# oresat-camera-board-v1.net
KiCad netlist of a schematic drawn in EAGLE
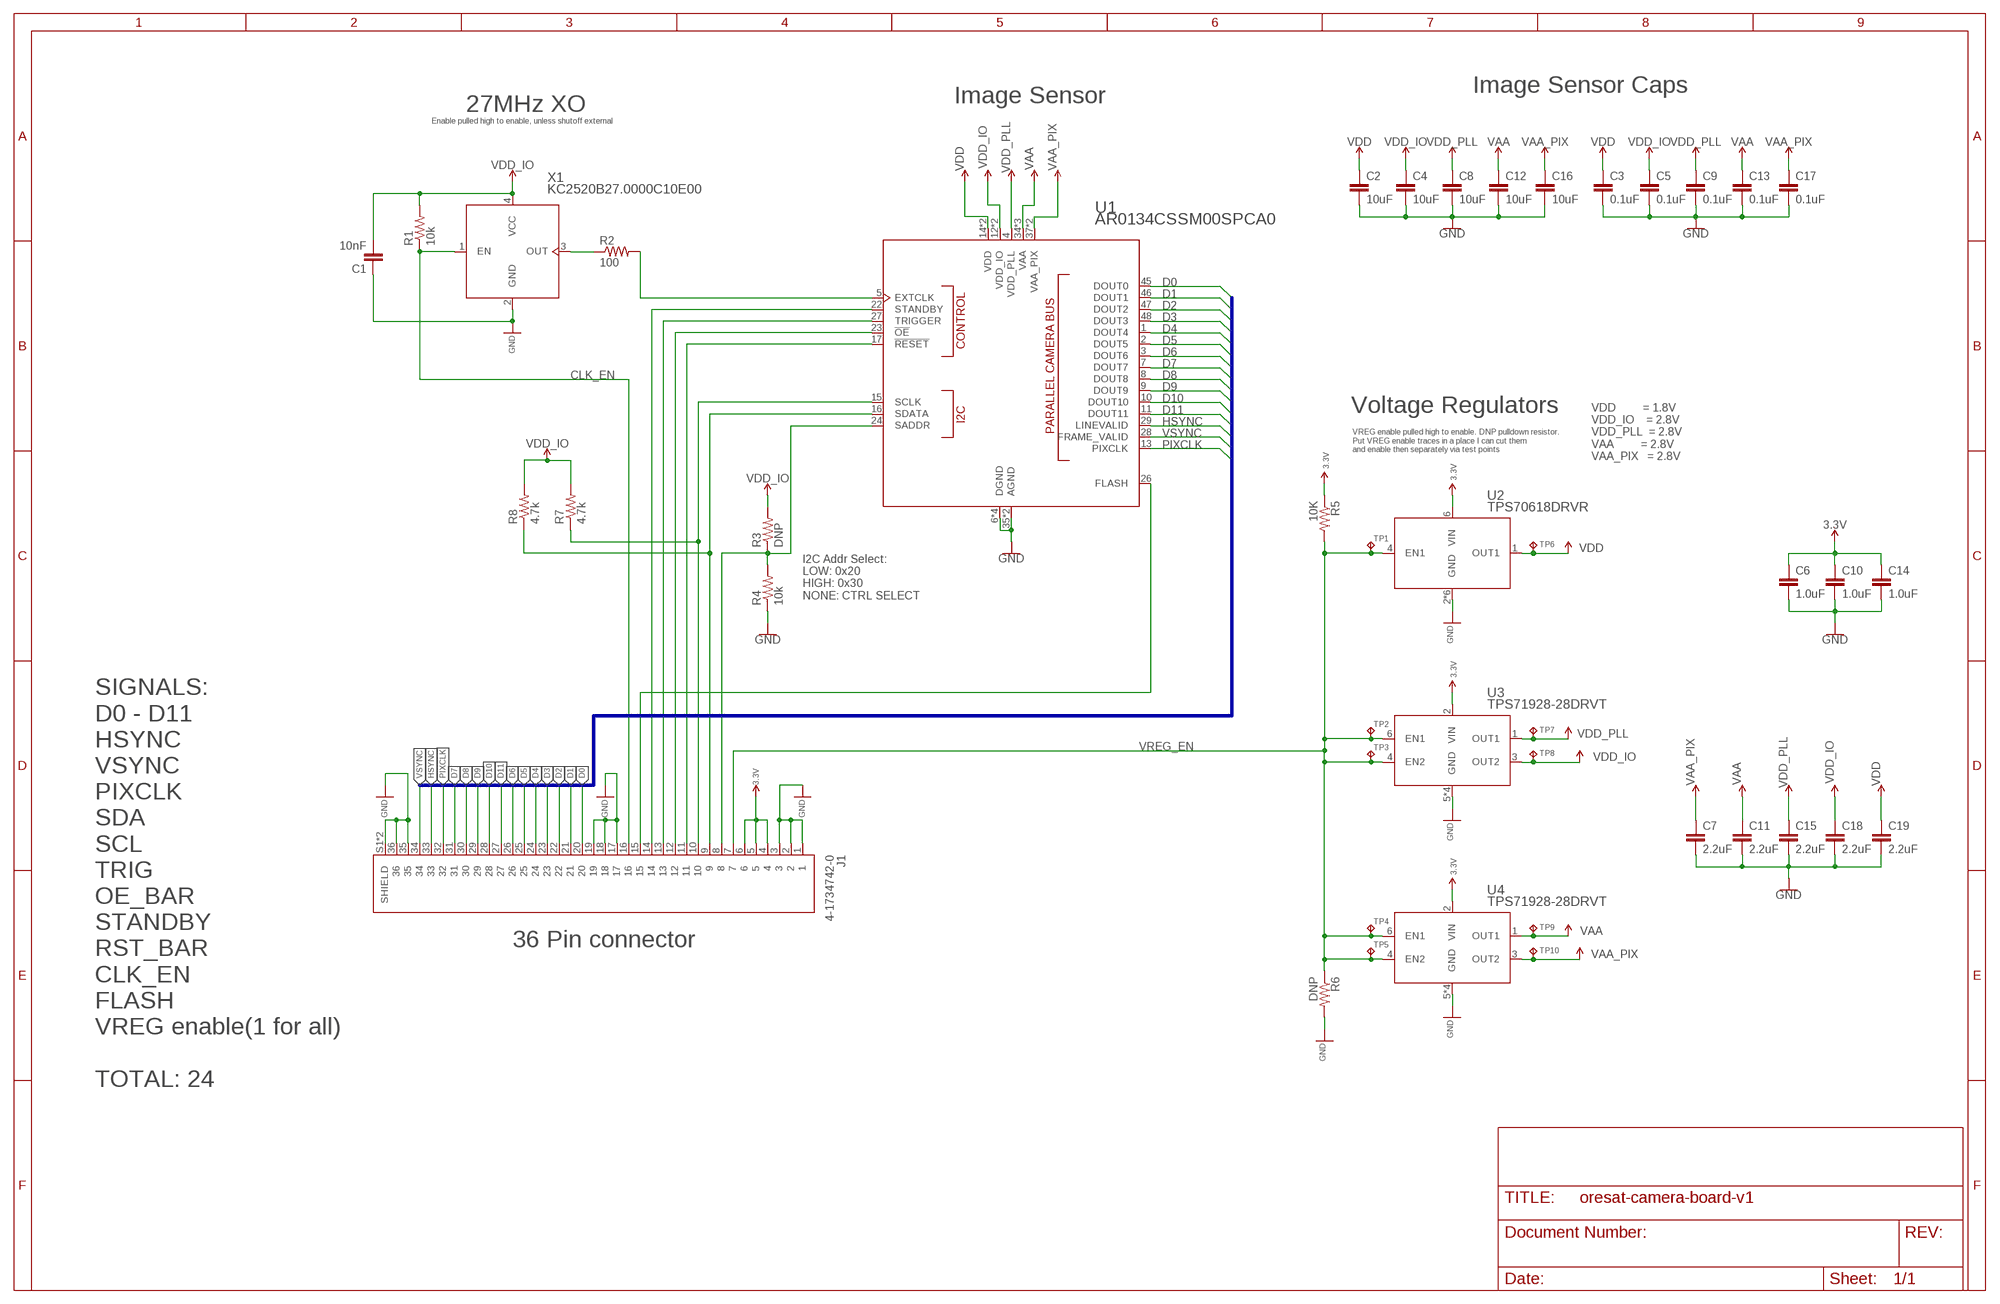
[diagram p0: schematic, sheet 1]

(export (version "E")
  (design (tool "Eeschema 10.0.6"))
  (components
    (comp (ref "C1")
      (value "10nF")
      (footprint "eagle-import:.0402-A-NOSILK")
      (libsource (lib "eagle-import") (part "C-EU0402-A-NOSILK"))
    )
    (comp (ref "C2")
      (value "10uF")
      (footprint "eagle-import:.0603-C-NOSILK")
      (libsource (lib "eagle-import") (part "C-EU0603-C-NOSILK"))
    )
    (comp (ref "C3")
      (value "0.1uF")
      (footprint "eagle-import:.0402-B-NOSILK")
      (libsource (lib "eagle-import") (part "C-EU0402-B-NOSILK"))
    )
    (comp (ref "C4")
      (value "10uF")
      (footprint "eagle-import:.0603-C-NOSILK")
      (libsource (lib "eagle-import") (part "C-EU0603-C-NOSILK"))
    )
    (comp (ref "C5")
      (value "0.1uF")
      (footprint "eagle-import:.0402-B-NOSILK")
      (libsource (lib "eagle-import") (part "C-EU0402-B-NOSILK"))
    )
    (comp (ref "C6")
      (value "1.0uF")
      (footprint "eagle-import:.0603-C-NOSILK")
      (libsource (lib "eagle-import") (part "C-EU0603-C-NOSILK"))
    )
    (comp (ref "C7")
      (value "2.2uF")
      (footprint "eagle-import:.0603-C-NOSILK")
      (libsource (lib "eagle-import") (part "C-EU0603-C-NOSILK"))
    )
    (comp (ref "C8")
      (value "10uF")
      (footprint "eagle-import:.0603-C-NOSILK")
      (libsource (lib "eagle-import") (part "C-EU0603-C-NOSILK"))
    )
    (comp (ref "C9")
      (value "0.1uF")
      (footprint "eagle-import:.0402-B-NOSILK")
      (libsource (lib "eagle-import") (part "C-EU0402-B-NOSILK"))
    )
    (comp (ref "C10")
      (value "1.0uF")
      (footprint "eagle-import:.0603-C-NOSILK")
      (libsource (lib "eagle-import") (part "C-EU0603-C-NOSILK"))
    )
    (comp (ref "C11")
      (value "2.2uF")
      (footprint "eagle-import:.0603-C-NOSILK")
      (libsource (lib "eagle-import") (part "C-EU0603-C-NOSILK"))
    )
    (comp (ref "C12")
      (value "10uF")
      (footprint "eagle-import:.0603-C-NOSILK")
      (libsource (lib "eagle-import") (part "C-EU0603-C-NOSILK"))
    )
    (comp (ref "C13")
      (value "0.1uF")
      (footprint "eagle-import:.0402-B-NOSILK")
      (libsource (lib "eagle-import") (part "C-EU0402-B-NOSILK"))
    )
    (comp (ref "C14")
      (value "1.0uF")
      (footprint "eagle-import:.0603-C-NOSILK")
      (libsource (lib "eagle-import") (part "C-EU0603-C-NOSILK"))
    )
    (comp (ref "C15")
      (value "2.2uF")
      (footprint "eagle-import:.0603-C-NOSILK")
      (libsource (lib "eagle-import") (part "C-EU0603-C-NOSILK"))
    )
    (comp (ref "C16")
      (value "10uF")
      (footprint "eagle-import:.0603-C-NOSILK")
      (libsource (lib "eagle-import") (part "C-EU0603-C-NOSILK"))
    )
    (comp (ref "C17")
      (value "0.1uF")
      (footprint "eagle-import:.0402-B-NOSILK")
      (libsource (lib "eagle-import") (part "C-EU0402-B-NOSILK"))
    )
    (comp (ref "C18")
      (value "2.2uF")
      (footprint "eagle-import:.0603-C-NOSILK")
      (libsource (lib "eagle-import") (part "C-EU0603-C-NOSILK"))
    )
    (comp (ref "C19")
      (value "2.2uF")
      (footprint "eagle-import:.0603-C-NOSILK")
      (libsource (lib "eagle-import") (part "C-EU0603-C-NOSILK"))
    )
    (comp (ref "J1")
      (value "4-1734742-0")
      (footprint "eagle-import:TE_4-1734742-0")
      (fields (field (name "DIGI-KEY_PART_NUMBER") "A100242CT-ND") (field (name "MF") "TE Connectivity"))
      (libsource (lib "eagle-import") (part "4-1734742-0"))
    )
    (comp (ref "R1")
      (value "10k")
      (footprint "eagle-import:.0402-B")
      (libsource (lib "eagle-import") (part "R-US_0402-B"))
    )
    (comp (ref "R2")
      (value "100")
      (footprint "eagle-import:.0402-B")
      (libsource (lib "eagle-import") (part "R-US_0402-B"))
    )
    (comp (ref "R3")
      (value "DNP")
      (footprint "eagle-import:.0402-B")
      (libsource (lib "eagle-import") (part "R-US_0402-B"))
    )
    (comp (ref "R4")
      (value "10k")
      (footprint "eagle-import:.0402-B")
      (libsource (lib "eagle-import") (part "R-US_0402-B"))
    )
    (comp (ref "R5")
      (value "10K")
      (footprint "eagle-import:.0402-B")
      (libsource (lib "eagle-import") (part "R-US_0402-B"))
    )
    (comp (ref "R6")
      (value "DNP")
      (footprint "eagle-import:.0402-B")
      (libsource (lib "eagle-import") (part "R-US_0402-B"))
    )
    (comp (ref "R7")
      (value "4.7k")
      (footprint "eagle-import:.0402-B")
      (libsource (lib "eagle-import") (part "R-US_0402-B"))
    )
    (comp (ref "R8")
      (value "4.7k")
      (footprint "eagle-import:.0402-B")
      (libsource (lib "eagle-import") (part "R-US_0402-B"))
    )
    (comp (ref "TP1")
      (value "TPTP06R")
      (footprint "eagle-import:TP06R")
      (libsource (lib "eagle-import") (part "TPTP06R"))
    )
    (comp (ref "TP2")
      (value "TPTP06R")
      (footprint "eagle-import:TP06R")
      (libsource (lib "eagle-import") (part "TPTP06R"))
    )
    (comp (ref "TP3")
      (value "TPTP06R")
      (footprint "eagle-import:TP06R")
      (libsource (lib "eagle-import") (part "TPTP06R"))
    )
    (comp (ref "TP4")
      (value "TPTP06R")
      (footprint "eagle-import:TP06R")
      (libsource (lib "eagle-import") (part "TPTP06R"))
    )
    (comp (ref "TP5")
      (value "TPTP06R")
      (footprint "eagle-import:TP06R")
      (libsource (lib "eagle-import") (part "TPTP06R"))
    )
    (comp (ref "TP6")
      (value "TPTP06R")
      (footprint "eagle-import:TP06R")
      (libsource (lib "eagle-import") (part "TPTP06R"))
    )
    (comp (ref "TP7")
      (value "TPTP06R")
      (footprint "eagle-import:TP06R")
      (libsource (lib "eagle-import") (part "TPTP06R"))
    )
    (comp (ref "TP8")
      (value "TPTP06R")
      (footprint "eagle-import:TP06R")
      (libsource (lib "eagle-import") (part "TPTP06R"))
    )
    (comp (ref "TP9")
      (value "TPTP06R")
      (footprint "eagle-import:TP06R")
      (libsource (lib "eagle-import") (part "TPTP06R"))
    )
    (comp (ref "TP10")
      (value "TPTP06R")
      (footprint "eagle-import:TP06R")
      (libsource (lib "eagle-import") (part "TPTP06R"))
    )
    (comp (ref "U1")
      (value "AR0134CSSM00SPCA0")
      (footprint "eagle-import:AR0134CSSM00SPCA0")
      (libsource (lib "eagle-import") (part "AR0134CSSM00SPCA0"))
    )
    (comp (ref "U2")
      (value "TPS70618DRVR")
      (footprint "eagle-import:DRV6_1P6X1")
      (fields (field (name "MANUFACTURER_PART_NUMBER") "TPS7192828DRVT"))
      (libsource (lib "eagle-import") (part "TPS70618DRVR"))
    )
    (comp (ref "U3")
      (value "TPS71928-28DRVT")
      (footprint "eagle-import:DRV6_1P6X1")
      (fields (field (name "MANUFACTURER_PART_NUMBER") "TPS7192828DRVT"))
      (libsource (lib "eagle-import") (part "TPS71928-28DRVT"))
    )
    (comp (ref "U4")
      (value "TPS71928-28DRVT")
      (footprint "eagle-import:DRV6_1P6X1")
      (fields (field (name "MANUFACTURER_PART_NUMBER") "TPS7192828DRVT"))
      (libsource (lib "eagle-import") (part "TPS71928-28DRVT"))
    )
    (comp (ref "X1")
      (value "KC2520B27.0000C10E00")
      (footprint "eagle-import:OSC_KYOCERA_KC2520B")
      (libsource (lib "eagle-import") (part "KC2520B27.0000C10E00"))
    )
  )
  (nets
    (net (code "1") (name "/CLK_EN") (class "Default")
      (node (ref "J1") (pin "16") (pinfunction "16_16") (pintype "passive"))
      (node (ref "R1") (pin "1") (pinfunction "1_1") (pintype "passive"))
      (node (ref "X1") (pin "1") (pinfunction "EN_1") (pintype "passive"))
    )
    (net (code "2") (name "/VREG_EN") (class "Default")
      (node (ref "J1") (pin "7") (pinfunction "7_7") (pintype "passive"))
      (node (ref "R5") (pin "2") (pinfunction "2_2") (pintype "passive"))
      (node (ref "R6") (pin "1") (pinfunction "1_1") (pintype "passive"))
      (node (ref "TP1") (pin "TP") (pinfunction "TP_TP") (pintype "input"))
      (node (ref "TP2") (pin "TP") (pinfunction "TP_TP") (pintype "input"))
      (node (ref "TP3") (pin "TP") (pinfunction "TP_TP") (pintype "input"))
      (node (ref "TP4") (pin "TP") (pinfunction "TP_TP") (pintype "input"))
      (node (ref "TP5") (pin "TP") (pinfunction "TP_TP") (pintype "input"))
      (node (ref "U2") (pin "4") (pinfunction "EN1_4") (pintype "passive"))
      (node (ref "U3") (pin "4") (pinfunction "EN2_4") (pintype "passive"))
      (node (ref "U3") (pin "6") (pinfunction "EN1_6") (pintype "passive"))
      (node (ref "U4") (pin "4") (pinfunction "EN2_4") (pintype "passive"))
      (node (ref "U4") (pin "6") (pinfunction "EN1_6") (pintype "passive"))
    )
    (net (code "3") (name "3.3V") (class "Default")
      (node (ref "C10") (pin "1") (pinfunction "1_1") (pintype "passive"))
      (node (ref "C14") (pin "1") (pinfunction "1_1") (pintype "passive"))
      (node (ref "C6") (pin "1") (pinfunction "1_1") (pintype "passive"))
      (node (ref "J1") (pin "4") (pinfunction "4_4") (pintype "passive"))
      (node (ref "J1") (pin "5") (pinfunction "5_5") (pintype "passive"))
      (node (ref "J1") (pin "6") (pinfunction "6_6") (pintype "passive"))
      (node (ref "R5") (pin "1") (pinfunction "1_1") (pintype "passive"))
      (node (ref "U2") (pin "6") (pinfunction "VIN_6") (pintype "input"))
      (node (ref "U3") (pin "2") (pinfunction "VIN_2") (pintype "power_in"))
      (node (ref "U4") (pin "2") (pinfunction "VIN_2") (pintype "power_in"))
    )
    (net (code "4") (name "D0") (class "Default")
      (node (ref "J1") (pin "20") (pinfunction "20_20") (pintype "passive"))
      (node (ref "U1") (pin "45") (pinfunction "DOUT0_45") (pintype "bidirectional"))
    )
    (net (code "5") (name "D1") (class "Default")
      (node (ref "J1") (pin "21") (pinfunction "21_21") (pintype "passive"))
      (node (ref "U1") (pin "46") (pinfunction "DOUT1_46") (pintype "bidirectional"))
    )
    (net (code "6") (name "D2") (class "Default")
      (node (ref "J1") (pin "22") (pinfunction "22_22") (pintype "passive"))
      (node (ref "U1") (pin "47") (pinfunction "DOUT2_47") (pintype "bidirectional"))
    )
    (net (code "7") (name "D3") (class "Default")
      (node (ref "J1") (pin "23") (pinfunction "23_23") (pintype "passive"))
      (node (ref "U1") (pin "48") (pinfunction "DOUT3_48") (pintype "bidirectional"))
    )
    (net (code "8") (name "D4") (class "Default")
      (node (ref "J1") (pin "24") (pinfunction "24_24") (pintype "passive"))
      (node (ref "U1") (pin "1") (pinfunction "DOUT4_1") (pintype "bidirectional"))
    )
    (net (code "9") (name "D5") (class "Default")
      (node (ref "J1") (pin "25") (pinfunction "25_25") (pintype "passive"))
      (node (ref "U1") (pin "2") (pinfunction "DOUT5_2") (pintype "bidirectional"))
    )
    (net (code "10") (name "D6") (class "Default")
      (node (ref "J1") (pin "26") (pinfunction "26_26") (pintype "passive"))
      (node (ref "U1") (pin "3") (pinfunction "DOUT6_3") (pintype "bidirectional"))
    )
    (net (code "11") (name "D7") (class "Default")
      (node (ref "J1") (pin "31") (pinfunction "31_31") (pintype "passive"))
      (node (ref "U1") (pin "7") (pinfunction "DOUT7_7") (pintype "bidirectional"))
    )
    (net (code "12") (name "D8") (class "Default")
      (node (ref "J1") (pin "30") (pinfunction "30_30") (pintype "passive"))
      (node (ref "U1") (pin "8") (pinfunction "DOUT8_8") (pintype "bidirectional"))
    )
    (net (code "13") (name "D9") (class "Default")
      (node (ref "J1") (pin "29") (pinfunction "29_29") (pintype "passive"))
      (node (ref "U1") (pin "9") (pinfunction "DOUT9_9") (pintype "bidirectional"))
    )
    (net (code "14") (name "D10") (class "Default")
      (node (ref "J1") (pin "28") (pinfunction "28_28") (pintype "passive"))
      (node (ref "U1") (pin "10") (pinfunction "DOUT10_10") (pintype "bidirectional"))
    )
    (net (code "15") (name "D11") (class "Default")
      (node (ref "J1") (pin "27") (pinfunction "27_27") (pintype "passive"))
      (node (ref "U1") (pin "11") (pinfunction "DOUT11_11") (pintype "bidirectional"))
    )
    (net (code "16") (name "GND") (class "Default")
      (node (ref "C1") (pin "1") (pinfunction "1_1") (pintype "passive"))
      (node (ref "C10") (pin "2") (pinfunction "2_2") (pintype "passive"))
      (node (ref "C11") (pin "2") (pinfunction "2_2") (pintype "passive"))
      (node (ref "C12") (pin "2") (pinfunction "2_2") (pintype "passive"))
      (node (ref "C13") (pin "2") (pinfunction "2_2") (pintype "passive"))
      (node (ref "C14") (pin "2") (pinfunction "2_2") (pintype "passive"))
      (node (ref "C15") (pin "2") (pinfunction "2_2") (pintype "passive"))
      (node (ref "C16") (pin "2") (pinfunction "2_2") (pintype "passive"))
      (node (ref "C17") (pin "2") (pinfunction "2_2") (pintype "passive"))
      (node (ref "C18") (pin "2") (pinfunction "2_2") (pintype "passive"))
      (node (ref "C19") (pin "2") (pinfunction "2_2") (pintype "passive"))
      (node (ref "C2") (pin "2") (pinfunction "2_2") (pintype "passive"))
      (node (ref "C3") (pin "2") (pinfunction "2_2") (pintype "passive"))
      (node (ref "C4") (pin "2") (pinfunction "2_2") (pintype "passive"))
      (node (ref "C5") (pin "2") (pinfunction "2_2") (pintype "passive"))
      (node (ref "C6") (pin "2") (pinfunction "2_2") (pintype "passive"))
      (node (ref "C7") (pin "2") (pinfunction "2_2") (pintype "passive"))
      (node (ref "C8") (pin "2") (pinfunction "2_2") (pintype "passive"))
      (node (ref "C9") (pin "2") (pinfunction "2_2") (pintype "passive"))
      (node (ref "J1") (pin "1") (pinfunction "1_1") (pintype "passive"))
      (node (ref "J1") (pin "17") (pinfunction "17_17") (pintype "passive"))
      (node (ref "J1") (pin "18") (pinfunction "18_18") (pintype "passive"))
      (node (ref "J1") (pin "19") (pinfunction "19_19") (pintype "passive"))
      (node (ref "J1") (pin "2") (pinfunction "2_2") (pintype "passive"))
      (node (ref "J1") (pin "3") (pinfunction "3_3") (pintype "passive"))
      (node (ref "J1") (pin "35") (pinfunction "35_35") (pintype "passive"))
      (node (ref "J1") (pin "36") (pinfunction "36_36") (pintype "passive"))
      (node (ref "J1") (pin "S1") (pinfunction "SHIELD_S1") (pintype "passive"))
      (node (ref "J1") (pin "S2") (pinfunction "SHIELD_S2") (pintype "passive"))
      (node (ref "R4") (pin "1") (pinfunction "1_1") (pintype "passive"))
      (node (ref "R6") (pin "2") (pinfunction "2_2") (pintype "passive"))
      (node (ref "U1") (pin "25") (pinfunction "DGND_25") (pintype "power_in"))
      (node (ref "U1") (pin "30") (pinfunction "DGND_30") (pintype "power_in"))
      (node (ref "U1") (pin "35") (pinfunction "AGND_35") (pintype "power_in"))
      (node (ref "U1") (pin "39") (pinfunction "AGND_39") (pintype "power_in"))
      (node (ref "U1") (pin "44") (pinfunction "DGND_44") (pintype "power_in"))
      (node (ref "U1") (pin "6") (pinfunction "DGND_6") (pintype "power_in"))
      (node (ref "U2") (pin "2") (pinfunction "GND_2") (pintype "power_in"))
      (node (ref "U2") (pin "3") (pinfunction "GND_3") (pintype "power_in"))
      (node (ref "U2") (pin "5") (pinfunction "GND_5") (pintype "power_in"))
      (node (ref "U2") (pin "7") (pinfunction "GND_7") (pintype "power_in"))
      (node (ref "U2") (pin "8") (pinfunction "GND_8") (pintype "power_in"))
      (node (ref "U2") (pin "9") (pinfunction "GND_9") (pintype "power_in"))
      (node (ref "U3") (pin "5") (pinfunction "GND_5") (pintype "power_in"))
      (node (ref "U3") (pin "7") (pinfunction "GND_7") (pintype "power_in"))
      (node (ref "U3") (pin "8") (pinfunction "GND_8") (pintype "power_in"))
      (node (ref "U3") (pin "9") (pinfunction "GND_9") (pintype "power_in"))
      (node (ref "U4") (pin "5") (pinfunction "GND_5") (pintype "power_in"))
      (node (ref "U4") (pin "7") (pinfunction "GND_7") (pintype "power_in"))
      (node (ref "U4") (pin "8") (pinfunction "GND_8") (pintype "power_in"))
      (node (ref "U4") (pin "9") (pinfunction "GND_9") (pintype "power_in"))
      (node (ref "X1") (pin "2") (pinfunction "GND_2") (pintype "power_in"))
    )
    (net (code "17") (name "HSYNC") (class "Default")
      (node (ref "J1") (pin "33") (pinfunction "33_33") (pintype "passive"))
      (node (ref "U1") (pin "29") (pinfunction "LINEVALID_29") (pintype "bidirectional"))
    )
    (net (code "18") (name "Net-(U1-EXTCLK)") (class "Default")
      (node (ref "R2") (pin "2") (pinfunction "2_2") (pintype "passive"))
      (node (ref "U1") (pin "5") (pinfunction "EXTCLK_5") (pintype "bidirectional"))
    )
    (net (code "19") (name "Net-(U1-FLASH)") (class "Default")
      (node (ref "J1") (pin "15") (pinfunction "15_15") (pintype "passive"))
      (node (ref "U1") (pin "26") (pinfunction "FLASH_26") (pintype "bidirectional"))
    )
    (net (code "20") (name "Net-(U1-SADDR)") (class "Default")
      (node (ref "J1") (pin "8") (pinfunction "8_8") (pintype "passive"))
      (node (ref "R3") (pin "1") (pinfunction "1_1") (pintype "passive"))
      (node (ref "R4") (pin "2") (pinfunction "2_2") (pintype "passive"))
      (node (ref "U1") (pin "24") (pinfunction "SADDR_24") (pintype "bidirectional"))
    )
    (net (code "21") (name "Net-(U1-SCLK)") (class "Default")
      (node (ref "J1") (pin "10") (pinfunction "10_10") (pintype "passive"))
      (node (ref "R7") (pin "1") (pinfunction "1_1") (pintype "passive"))
      (node (ref "U1") (pin "15") (pinfunction "SCLK_15") (pintype "bidirectional"))
    )
    (net (code "22") (name "Net-(U1-SDATA)") (class "Default")
      (node (ref "J1") (pin "9") (pinfunction "9_9") (pintype "passive"))
      (node (ref "R8") (pin "1") (pinfunction "1_1") (pintype "passive"))
      (node (ref "U1") (pin "16") (pinfunction "SDATA_16") (pintype "bidirectional"))
    )
    (net (code "23") (name "Net-(U1-STANDBY)") (class "Default")
      (node (ref "J1") (pin "14") (pinfunction "14_14") (pintype "passive"))
      (node (ref "U1") (pin "22") (pinfunction "STANDBY_22") (pintype "bidirectional"))
    )
    (net (code "24") (name "Net-(U1-TRIGGER)") (class "Default")
      (node (ref "J1") (pin "13") (pinfunction "13_13") (pintype "passive"))
      (node (ref "U1") (pin "27") (pinfunction "TRIGGER_27") (pintype "bidirectional"))
    )
    (net (code "25") (name "Net-(U1-~{OE})") (class "Default")
      (node (ref "J1") (pin "12") (pinfunction "12_12") (pintype "passive"))
      (node (ref "U1") (pin "23") (pinfunction "~{OE}_23") (pintype "bidirectional"))
    )
    (net (code "26") (name "Net-(U1-~{RESET})") (class "Default")
      (node (ref "J1") (pin "11") (pinfunction "11_11") (pintype "passive"))
      (node (ref "U1") (pin "17") (pinfunction "~{RESET}_17") (pintype "bidirectional"))
    )
    (net (code "27") (name "Net-(X1-OUT)") (class "Default")
      (node (ref "R2") (pin "1") (pinfunction "1_1") (pintype "passive"))
      (node (ref "X1") (pin "3") (pinfunction "OUT_3") (pintype "output"))
    )
    (net (code "28") (name "PIXCLK") (class "Default")
      (node (ref "J1") (pin "32") (pinfunction "32_32") (pintype "passive"))
      (node (ref "U1") (pin "13") (pinfunction "PIXCLK_13") (pintype "bidirectional"))
    )
    (net (code "29") (name "VAA") (class "Default")
      (node (ref "C11") (pin "1") (pinfunction "1_1") (pintype "passive"))
      (node (ref "C12") (pin "1") (pinfunction "1_1") (pintype "passive"))
      (node (ref "C13") (pin "1") (pinfunction "1_1") (pintype "passive"))
      (node (ref "TP9") (pin "TP") (pinfunction "TP_TP") (pintype "input"))
      (node (ref "U1") (pin "34") (pinfunction "VAA_34") (pintype "power_in"))
      (node (ref "U1") (pin "36") (pinfunction "VAA_36") (pintype "power_in"))
      (node (ref "U1") (pin "40") (pinfunction "VAA_40") (pintype "power_in"))
      (node (ref "U4") (pin "1") (pinfunction "OUT1_1") (pintype "power_in"))
    )
    (net (code "30") (name "VAA_PIX") (class "Default")
      (node (ref "C16") (pin "1") (pinfunction "1_1") (pintype "passive"))
      (node (ref "C17") (pin "1") (pinfunction "1_1") (pintype "passive"))
      (node (ref "C7") (pin "1") (pinfunction "1_1") (pintype "passive"))
      (node (ref "TP10") (pin "TP") (pinfunction "TP_TP") (pintype "input"))
      (node (ref "U1") (pin "37") (pinfunction "VAA_PIX_37") (pintype "power_in"))
      (node (ref "U1") (pin "38") (pinfunction "VAA_PIX_38") (pintype "power_in"))
      (node (ref "U4") (pin "3") (pinfunction "OUT2_3") (pintype "power_in"))
    )
    (net (code "31") (name "VDD") (class "Default")
      (node (ref "C19") (pin "1") (pinfunction "1_1") (pintype "passive"))
      (node (ref "C2") (pin "1") (pinfunction "1_1") (pintype "passive"))
      (node (ref "C3") (pin "1") (pinfunction "1_1") (pintype "passive"))
      (node (ref "TP6") (pin "TP") (pinfunction "TP_TP") (pintype "input"))
      (node (ref "U1") (pin "14") (pinfunction "VDD_14") (pintype "power_in"))
      (node (ref "U1") (pin "19") (pinfunction "VDD_19") (pintype "power_in"))
      (node (ref "U2") (pin "1") (pinfunction "OUT1_1") (pintype "passive"))
    )
    (net (code "32") (name "VDD_IO") (class "Default")
      (node (ref "C1") (pin "2") (pinfunction "2_2") (pintype "passive"))
      (node (ref "C18") (pin "1") (pinfunction "1_1") (pintype "passive"))
      (node (ref "C4") (pin "1") (pinfunction "1_1") (pintype "passive"))
      (node (ref "C5") (pin "1") (pinfunction "1_1") (pintype "passive"))
      (node (ref "R1") (pin "2") (pinfunction "2_2") (pintype "passive"))
      (node (ref "R3") (pin "2") (pinfunction "2_2") (pintype "passive"))
      (node (ref "R7") (pin "2") (pinfunction "2_2") (pintype "passive"))
      (node (ref "R8") (pin "2") (pinfunction "2_2") (pintype "passive"))
      (node (ref "TP8") (pin "TP") (pinfunction "TP_TP") (pintype "input"))
      (node (ref "U1") (pin "12") (pinfunction "VDD_IO_12") (pintype "power_in"))
      (node (ref "U1") (pin "18") (pinfunction "VDD_IO_18") (pintype "power_in"))
      (node (ref "U3") (pin "3") (pinfunction "OUT2_3") (pintype "power_in"))
      (node (ref "X1") (pin "4") (pinfunction "VCC_4") (pintype "power_in"))
    )
    (net (code "33") (name "VDD_PLL") (class "Default")
      (node (ref "C15") (pin "1") (pinfunction "1_1") (pintype "passive"))
      (node (ref "C8") (pin "1") (pinfunction "1_1") (pintype "passive"))
      (node (ref "C9") (pin "1") (pinfunction "1_1") (pintype "passive"))
      (node (ref "TP7") (pin "TP") (pinfunction "TP_TP") (pintype "input"))
      (node (ref "U1") (pin "4") (pinfunction "VDD_PLL_4") (pintype "power_in"))
      (node (ref "U3") (pin "1") (pinfunction "OUT1_1") (pintype "power_in"))
    )
    (net (code "34") (name "VSYNC") (class "Default")
      (node (ref "J1") (pin "34") (pinfunction "34_34") (pintype "passive"))
      (node (ref "U1") (pin "28") (pinfunction "FRAME_VALID_28") (pintype "bidirectional"))
    )
  )
)
